# DDR4_Connectors.net
KiCad netlist of a schematic drawn in Altium Designer
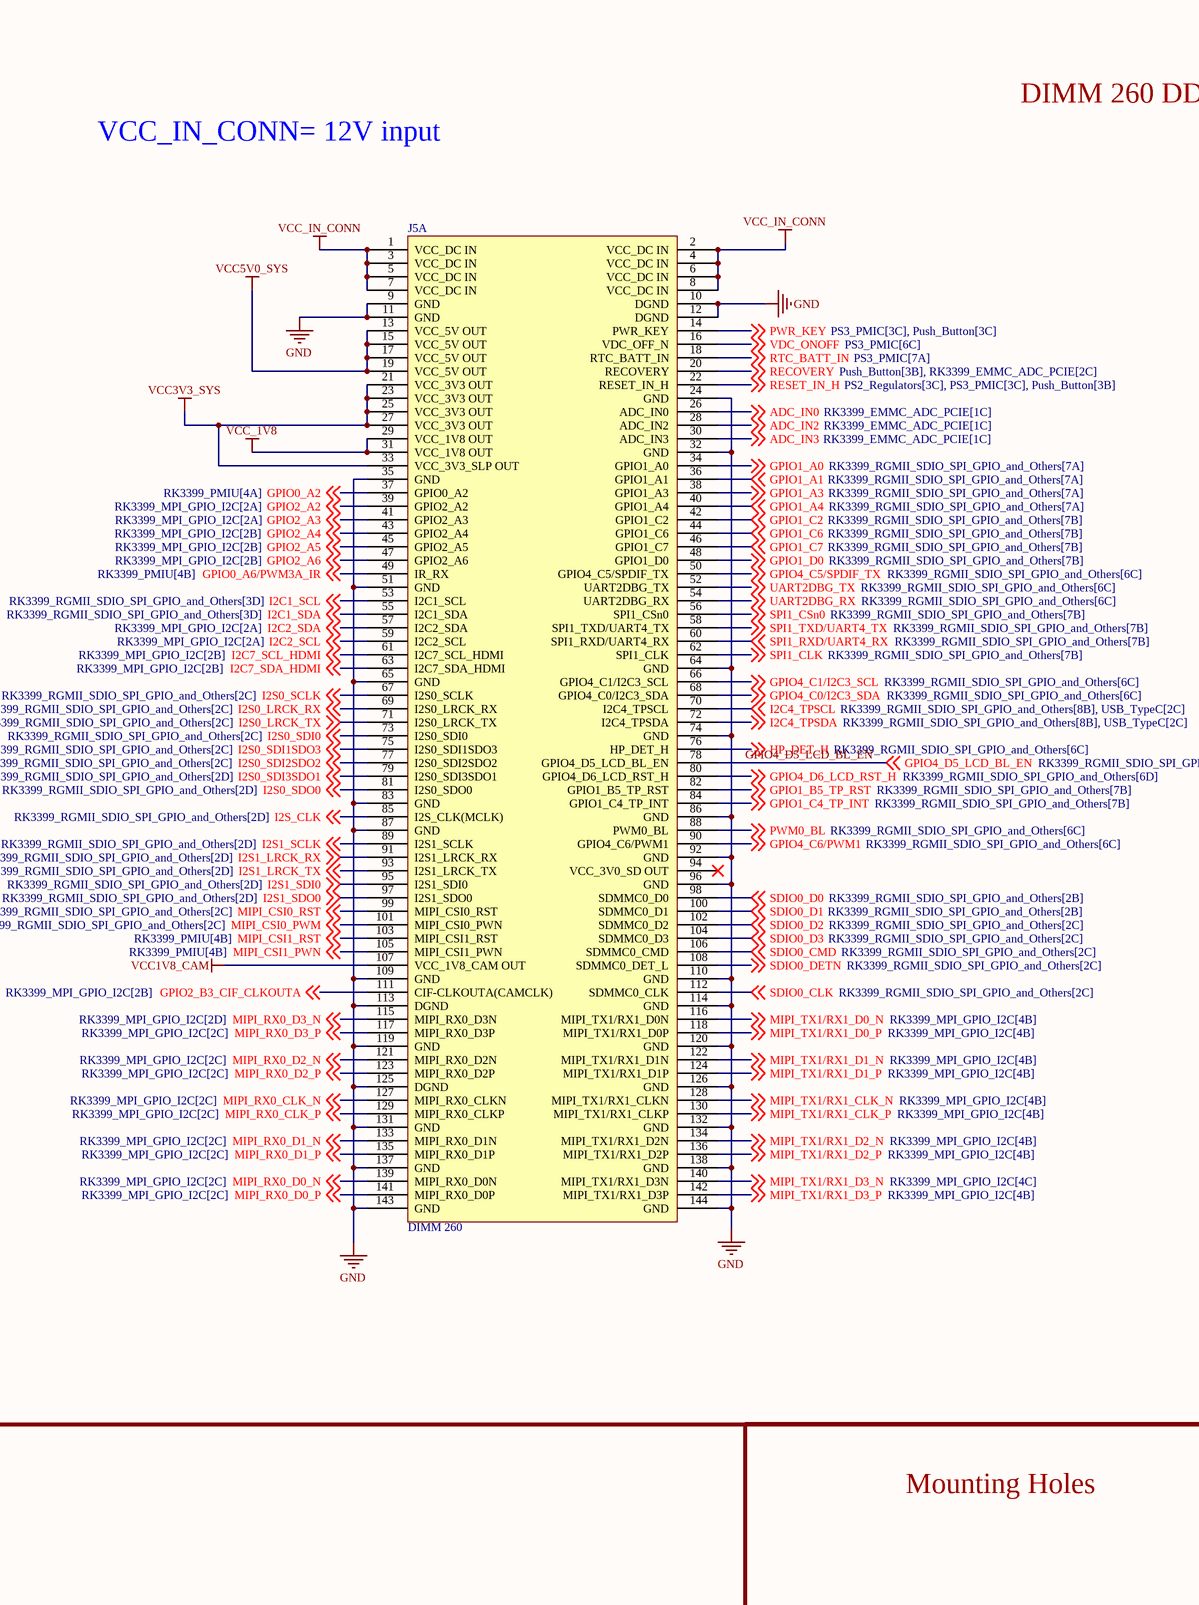
[diagram p0: DDR4_Connectors.SchDoc, left]
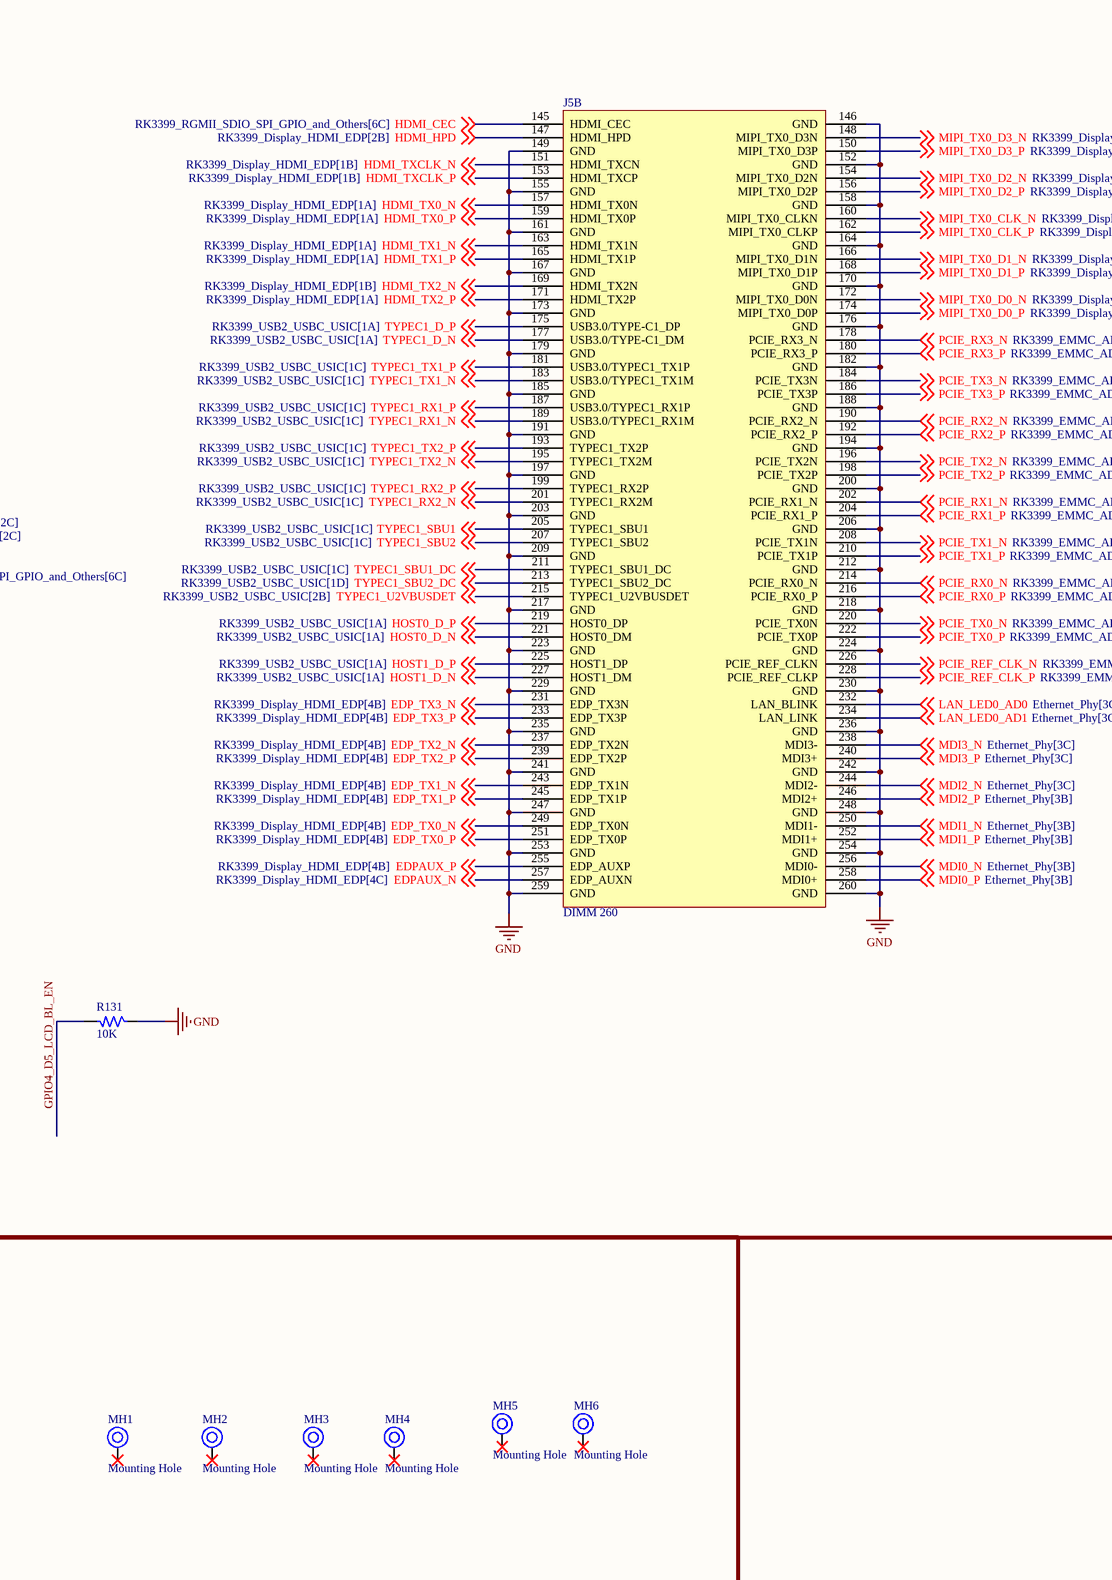
[diagram p1: DDR4_Connectors.SchDoc, right]

(export (version "E")
  (design (tool "Eeschema 10.0.6"))
  (components
    (comp (ref "J5")
      (value "DIMM 260")
      (footprint "DIMM260_DDR4")
      (description "Dimm 260 pin smd plating on pcb")
      (fields (field (name "MANUFACTURER") "NA"))
      (libsource (lib "EsteemPCB_SOM_Course_schlib") (part "CON-DIMM_260-SMD"))
    )
    (comp (ref "MH1")
      (value "Mounting Hole")
      (footprint "SOM_Mounting")
      (fields (field (name "MANUFACTURER PART NUMBER") "NA"))
      (libsource (lib "EsteemPCB_SOM_Course_schlib") (part "MH_3.5H_6D"))
    )
    (comp (ref "MH2")
      (value "Mounting Hole")
      (footprint "SOM_Mounting")
      (fields (field (name "MANUFACTURER PART NUMBER") "NA"))
      (libsource (lib "EsteemPCB_SOM_Course_schlib") (part "MH_3.5H_6D"))
    )
    (comp (ref "MH3")
      (value "Mounting Hole")
      (footprint "SOM_Mounting")
      (fields (field (name "MANUFACTURER PART NUMBER") "NA"))
      (libsource (lib "EsteemPCB_SOM_Course_schlib") (part "MH_3.5H_6D"))
    )
    (comp (ref "MH4")
      (value "Mounting Hole")
      (footprint "SOM_Mounting")
      (fields (field (name "MANUFACTURER PART NUMBER") "NA"))
      (libsource (lib "EsteemPCB_SOM_Course_schlib") (part "MH_3.5H_6D"))
    )
    (comp (ref "MH5")
      (value "Mounting Hole")
      (footprint "SOM_Mounting")
      (fields (field (name "MANUFACTURER PART NUMBER") "NA"))
      (libsource (lib "EsteemPCB_SOM_Course_schlib") (part "MH_3.5H_6D"))
    )
    (comp (ref "MH6")
      (value "Mounting Hole")
      (footprint "SOM_Mounting")
      (fields (field (name "MANUFACTURER PART NUMBER") "NA"))
      (libsource (lib "EsteemPCB_SOM_Course_schlib") (part "MH_3.5H_6D"))
    )
    (comp (ref "R131")
      (value "10K")
      (footprint "RES_0402")
      (description "10 kOhms ±1% 0.1W, 1/10W Chip Resistor 0402 (1005 Metric) Anti-Sulfur Thin Film")
      (fields
        (field (name "MANUFACTURER") "Vishay Beyschlag/Draloric/BC Components")
        (field (name "MANUFACTURER PART NUMBER") "MCS04020C1002FE000")
      )
      (libsource (lib "EsteemPCB_SOM_Course_schlib") (part "RES_10K-0.1W-1%-0402"))
    )
  )
  (nets
    (net (code "1") (name "ADC_IN0") (class "Default")
      (node (ref "J5") (pin "26") (pinfunction "ADC_IN0_26") (pintype "passive"))
    )
    (net (code "2") (name "ADC_IN2") (class "Default")
      (node (ref "J5") (pin "28") (pinfunction "ADC_IN2_28") (pintype "passive"))
    )
    (net (code "3") (name "ADC_IN3") (class "Default")
      (node (ref "J5") (pin "30") (pinfunction "ADC_IN3_30") (pintype "passive"))
    )
    (net (code "4") (name "EDPAUX_N") (class "Default")
      (node (ref "J5") (pin "257") (pinfunction "EDP_AUXN_257") (pintype "passive"))
    )
    (net (code "5") (name "EDPAUX_P") (class "Default")
      (node (ref "J5") (pin "255") (pinfunction "EDP_AUXP_255") (pintype "passive"))
    )
    (net (code "6") (name "EDP_TX0_N") (class "Default")
      (node (ref "J5") (pin "249") (pinfunction "EDP_TX0N_249") (pintype "passive"))
    )
    (net (code "7") (name "EDP_TX0_P") (class "Default")
      (node (ref "J5") (pin "251") (pinfunction "EDP_TX0P_251") (pintype "passive"))
    )
    (net (code "8") (name "EDP_TX1_N") (class "Default")
      (node (ref "J5") (pin "243") (pinfunction "EDP_TX1N_243") (pintype "passive"))
    )
    (net (code "9") (name "EDP_TX1_P") (class "Default")
      (node (ref "J5") (pin "245") (pinfunction "EDP_TX1P_245") (pintype "passive"))
    )
    (net (code "10") (name "EDP_TX2_N") (class "Default")
      (node (ref "J5") (pin "237") (pinfunction "EDP_TX2N_237") (pintype "passive"))
    )
    (net (code "11") (name "EDP_TX2_P") (class "Default")
      (node (ref "J5") (pin "239") (pinfunction "EDP_TX2P_239") (pintype "passive"))
    )
    (net (code "12") (name "EDP_TX3_N") (class "Default")
      (node (ref "J5") (pin "231") (pinfunction "EDP_TX3N_231") (pintype "passive"))
    )
    (net (code "13") (name "EDP_TX3_P") (class "Default")
      (node (ref "J5") (pin "233") (pinfunction "EDP_TX3P_233") (pintype "passive"))
    )
    (net (code "14") (name "GND") (class "Default")
      (node (ref "J5") (pin "10") (pinfunction "DGND_10") (pintype "passive"))
      (node (ref "J5") (pin "109") (pinfunction "GND_109") (pintype "passive"))
      (node (ref "J5") (pin "11") (pinfunction "GND_11") (pintype "passive"))
      (node (ref "J5") (pin "110") (pinfunction "GND_110") (pintype "passive"))
      (node (ref "J5") (pin "113") (pinfunction "DGND_113") (pintype "passive"))
      (node (ref "J5") (pin "114") (pinfunction "GND_114") (pintype "passive"))
      (node (ref "J5") (pin "119") (pinfunction "GND_119") (pintype "passive"))
      (node (ref "J5") (pin "12") (pinfunction "DGND_12") (pintype "passive"))
      (node (ref "J5") (pin "120") (pinfunction "GND_120") (pintype "passive"))
      (node (ref "J5") (pin "125") (pinfunction "DGND_125") (pintype "passive"))
      (node (ref "J5") (pin "126") (pinfunction "GND_126") (pintype "passive"))
      (node (ref "J5") (pin "131") (pinfunction "GND_131") (pintype "passive"))
      (node (ref "J5") (pin "132") (pinfunction "GND_132") (pintype "passive"))
      (node (ref "J5") (pin "137") (pinfunction "GND_137") (pintype "passive"))
      (node (ref "J5") (pin "138") (pinfunction "GND_138") (pintype "passive"))
      (node (ref "J5") (pin "143") (pinfunction "GND_143") (pintype "passive"))
      (node (ref "J5") (pin "144") (pinfunction "GND_144") (pintype "passive"))
      (node (ref "J5") (pin "146") (pinfunction "GND_146") (pintype "passive"))
      (node (ref "J5") (pin "149") (pinfunction "GND_149") (pintype "passive"))
      (node (ref "J5") (pin "152") (pinfunction "GND_152") (pintype "passive"))
      (node (ref "J5") (pin "155") (pinfunction "GND_155") (pintype "passive"))
      (node (ref "J5") (pin "158") (pinfunction "GND_158") (pintype "passive"))
      (node (ref "J5") (pin "161") (pinfunction "GND_161") (pintype "passive"))
      (node (ref "J5") (pin "164") (pinfunction "GND_164") (pintype "passive"))
      (node (ref "J5") (pin "167") (pinfunction "GND_167") (pintype "passive"))
      (node (ref "J5") (pin "170") (pinfunction "GND_170") (pintype "passive"))
      (node (ref "J5") (pin "173") (pinfunction "GND_173") (pintype "passive"))
      (node (ref "J5") (pin "176") (pinfunction "GND_176") (pintype "passive"))
      (node (ref "J5") (pin "179") (pinfunction "GND_179") (pintype "passive"))
      (node (ref "J5") (pin "182") (pinfunction "GND_182") (pintype "passive"))
      (node (ref "J5") (pin "185") (pinfunction "GND_185") (pintype "passive"))
      (node (ref "J5") (pin "188") (pinfunction "GND_188") (pintype "passive"))
      (node (ref "J5") (pin "191") (pinfunction "GND_191") (pintype "passive"))
      (node (ref "J5") (pin "194") (pinfunction "GND_194") (pintype "passive"))
      (node (ref "J5") (pin "197") (pinfunction "GND_197") (pintype "passive"))
      (node (ref "J5") (pin "200") (pinfunction "GND_200") (pintype "passive"))
      (node (ref "J5") (pin "203") (pinfunction "GND_203") (pintype "passive"))
      (node (ref "J5") (pin "206") (pinfunction "GND_206") (pintype "passive"))
      (node (ref "J5") (pin "209") (pinfunction "GND_209") (pintype "passive"))
      (node (ref "J5") (pin "212") (pinfunction "GND_212") (pintype "passive"))
      (node (ref "J5") (pin "217") (pinfunction "GND_217") (pintype "passive"))
      (node (ref "J5") (pin "218") (pinfunction "GND_218") (pintype "passive"))
      (node (ref "J5") (pin "223") (pinfunction "GND_223") (pintype "passive"))
      (node (ref "J5") (pin "224") (pinfunction "GND_224") (pintype "passive"))
      (node (ref "J5") (pin "229") (pinfunction "GND_229") (pintype "passive"))
      (node (ref "J5") (pin "230") (pinfunction "GND_230") (pintype "passive"))
      (node (ref "J5") (pin "235") (pinfunction "GND_235") (pintype "passive"))
      (node (ref "J5") (pin "236") (pinfunction "GND_236") (pintype "passive"))
      (node (ref "J5") (pin "24") (pinfunction "GND_24") (pintype "passive"))
      (node (ref "J5") (pin "241") (pinfunction "GND_241") (pintype "passive"))
      (node (ref "J5") (pin "242") (pinfunction "GND_242") (pintype "passive"))
      (node (ref "J5") (pin "247") (pinfunction "GND_247") (pintype "passive"))
      (node (ref "J5") (pin "248") (pinfunction "GND_248") (pintype "passive"))
      (node (ref "J5") (pin "253") (pinfunction "GND_253") (pintype "passive"))
      (node (ref "J5") (pin "254") (pinfunction "GND_254") (pintype "passive"))
      (node (ref "J5") (pin "259") (pinfunction "GND_259") (pintype "passive"))
      (node (ref "J5") (pin "260") (pinfunction "GND_260") (pintype "passive"))
      (node (ref "J5") (pin "32") (pinfunction "GND_32") (pintype "passive"))
      (node (ref "J5") (pin "35") (pinfunction "GND_35") (pintype "passive"))
      (node (ref "J5") (pin "51") (pinfunction "GND_51") (pintype "passive"))
      (node (ref "J5") (pin "64") (pinfunction "GND_64") (pintype "passive"))
      (node (ref "J5") (pin "65") (pinfunction "GND_65") (pintype "passive"))
      (node (ref "J5") (pin "74") (pinfunction "GND_74") (pintype "passive"))
      (node (ref "J5") (pin "83") (pinfunction "GND_83") (pintype "passive"))
      (node (ref "J5") (pin "86") (pinfunction "GND_86") (pintype "passive"))
      (node (ref "J5") (pin "87") (pinfunction "GND_87") (pintype "passive"))
      (node (ref "J5") (pin "9") (pinfunction "GND_9") (pintype "passive"))
      (node (ref "J5") (pin "92") (pinfunction "GND_92") (pintype "passive"))
      (node (ref "J5") (pin "96") (pinfunction "GND_96") (pintype "passive"))
      (node (ref "R131") (pin "1") (pinfunction "1_1") (pintype "passive"))
    )
    (net (code "15") (name "GPIO0_A2") (class "Default")
      (node (ref "J5") (pin "37") (pinfunction "GPIO0_A2_37") (pintype "passive"))
    )
    (net (code "16") (name "GPIO0_A6{slash}PWM3A_IR") (class "Default")
      (node (ref "J5") (pin "49") (pinfunction "IR_RX_49") (pintype "passive"))
    )
    (net (code "17") (name "GPIO1_A0") (class "Default")
      (node (ref "J5") (pin "34") (pinfunction "GPIO1_A0_34") (pintype "passive"))
    )
    (net (code "18") (name "GPIO1_A1") (class "Default")
      (node (ref "J5") (pin "36") (pinfunction "GPIO1_A1_36") (pintype "passive"))
    )
    (net (code "19") (name "GPIO1_A3") (class "Default")
      (node (ref "J5") (pin "38") (pinfunction "GPIO1_A3_38") (pintype "passive"))
    )
    (net (code "20") (name "GPIO1_A4") (class "Default")
      (node (ref "J5") (pin "40") (pinfunction "GPIO1_A4_40") (pintype "passive"))
    )
    (net (code "21") (name "GPIO1_B5_TP_RST") (class "Default")
      (node (ref "J5") (pin "82") (pinfunction "GPIO1_B5_TP_RST_82") (pintype "passive"))
    )
    (net (code "22") (name "GPIO1_C2") (class "Default")
      (node (ref "J5") (pin "42") (pinfunction "GPIO1_C2_42") (pintype "passive"))
    )
    (net (code "23") (name "GPIO1_C4_TP_INT") (class "Default")
      (node (ref "J5") (pin "84") (pinfunction "GPIO1_C4_TP_INT_84") (pintype "passive"))
    )
    (net (code "24") (name "GPIO1_C6") (class "Default")
      (node (ref "J5") (pin "44") (pinfunction "GPIO1_C6_44") (pintype "passive"))
    )
    (net (code "25") (name "GPIO1_C7") (class "Default")
      (node (ref "J5") (pin "46") (pinfunction "GPIO1_C7_46") (pintype "passive"))
    )
    (net (code "26") (name "GPIO1_D0") (class "Default")
      (node (ref "J5") (pin "48") (pinfunction "GPIO1_D0_48") (pintype "passive"))
    )
    (net (code "27") (name "GPIO2_A2") (class "Default")
      (node (ref "J5") (pin "39") (pinfunction "GPIO2_A2_39") (pintype "passive"))
    )
    (net (code "28") (name "GPIO2_A3") (class "Default")
      (node (ref "J5") (pin "41") (pinfunction "GPIO2_A3_41") (pintype "passive"))
    )
    (net (code "29") (name "GPIO2_A4") (class "Default")
      (node (ref "J5") (pin "43") (pinfunction "GPIO2_A4_43") (pintype "passive"))
    )
    (net (code "30") (name "GPIO2_A5") (class "Default")
      (node (ref "J5") (pin "45") (pinfunction "GPIO2_A5_45") (pintype "passive"))
    )
    (net (code "31") (name "GPIO2_A6") (class "Default")
      (node (ref "J5") (pin "47") (pinfunction "GPIO2_A6_47") (pintype "passive"))
    )
    (net (code "32") (name "GPIO2_B3_CIF_CLKOUTA") (class "Default")
      (node (ref "J5") (pin "111") (pinfunction "CIF-CLKOUTA(CAMCLK)_111") (pintype "passive"))
    )
    (net (code "33") (name "GPIO4_C0{slash}I2C3_SDA") (class "Default")
      (node (ref "J5") (pin "68") (pinfunction "GPIO4_C0/I2C3_SDA_68") (pintype "passive"))
    )
    (net (code "34") (name "GPIO4_C1{slash}I2C3_SCL") (class "Default")
      (node (ref "J5") (pin "66") (pinfunction "GPIO4_C1/I2C3_SCL_66") (pintype "passive"))
    )
    (net (code "35") (name "GPIO4_C5{slash}SPDIF_TX") (class "Default")
      (node (ref "J5") (pin "50") (pinfunction "GPIO4_C5/SPDIF_TX_50") (pintype "passive"))
    )
    (net (code "36") (name "GPIO4_C6{slash}PWM1") (class "Default")
      (node (ref "J5") (pin "90") (pinfunction "GPIO4_C6/PWM1_90") (pintype "passive"))
    )
    (net (code "37") (name "GPIO4_D5_LCD_BL_EN") (class "Default")
      (node (ref "J5") (pin "78") (pinfunction "GPIO4_D5_LCD_BL_EN_78") (pintype "passive"))
      (node (ref "R131") (pin "2") (pinfunction "2_2") (pintype "passive"))
    )
    (net (code "38") (name "GPIO4_D6_LCD_RST_H") (class "Default")
      (node (ref "J5") (pin "80") (pinfunction "GPIO4_D6_LCD_RST_H_80") (pintype "passive"))
    )
    (net (code "39") (name "HDMI_CEC") (class "Default")
      (node (ref "J5") (pin "145") (pinfunction "HDMI_CEC_145") (pintype "passive"))
    )
    (net (code "40") (name "HDMI_HPD") (class "Default")
      (node (ref "J5") (pin "147") (pinfunction "HDMI_HPD_147") (pintype "passive"))
    )
    (net (code "41") (name "HDMI_TX0_N") (class "Default")
      (node (ref "J5") (pin "157") (pinfunction "HDMI_TX0N_157") (pintype "passive"))
    )
    (net (code "42") (name "HDMI_TX0_P") (class "Default")
      (node (ref "J5") (pin "159") (pinfunction "HDMI_TX0P_159") (pintype "passive"))
    )
    (net (code "43") (name "HDMI_TX1_N") (class "Default")
      (node (ref "J5") (pin "163") (pinfunction "HDMI_TX1N_163") (pintype "passive"))
    )
    (net (code "44") (name "HDMI_TX1_P") (class "Default")
      (node (ref "J5") (pin "165") (pinfunction "HDMI_TX1P_165") (pintype "passive"))
    )
    (net (code "45") (name "HDMI_TX2_N") (class "Default")
      (node (ref "J5") (pin "169") (pinfunction "HDMI_TX2N_169") (pintype "passive"))
    )
    (net (code "46") (name "HDMI_TX2_P") (class "Default")
      (node (ref "J5") (pin "171") (pinfunction "HDMI_TX2P_171") (pintype "passive"))
    )
    (net (code "47") (name "HDMI_TXCLK_N") (class "Default")
      (node (ref "J5") (pin "151") (pinfunction "HDMI_TXCN_151") (pintype "passive"))
    )
    (net (code "48") (name "HDMI_TXCLK_P") (class "Default")
      (node (ref "J5") (pin "153") (pinfunction "HDMI_TXCP_153") (pintype "passive"))
    )
    (net (code "49") (name "HOST0_D_N") (class "Default")
      (node (ref "J5") (pin "221") (pinfunction "HOST0_DM_221") (pintype "passive"))
    )
    (net (code "50") (name "HOST0_D_P") (class "Default")
      (node (ref "J5") (pin "219") (pinfunction "HOST0_DP_219") (pintype "passive"))
    )
    (net (code "51") (name "HOST1_D_N") (class "Default")
      (node (ref "J5") (pin "227") (pinfunction "HOST1_DM_227") (pintype "passive"))
    )
    (net (code "52") (name "HOST1_D_P") (class "Default")
      (node (ref "J5") (pin "225") (pinfunction "HOST1_DP_225") (pintype "passive"))
    )
    (net (code "53") (name "HP_DET_H") (class "Default")
      (node (ref "J5") (pin "76") (pinfunction "HP_DET_H_76") (pintype "passive"))
    )
    (net (code "54") (name "I2C1_SCL") (class "Default")
      (node (ref "J5") (pin "53") (pinfunction "I2C1_SCL_53") (pintype "passive"))
    )
    (net (code "55") (name "I2C1_SDA") (class "Default")
      (node (ref "J5") (pin "55") (pinfunction "I2C1_SDA_55") (pintype "passive"))
    )
    (net (code "56") (name "I2C2_SCL") (class "Default")
      (node (ref "J5") (pin "59") (pinfunction "I2C2_SCL_59") (pintype "passive"))
    )
    (net (code "57") (name "I2C2_SDA") (class "Default")
      (node (ref "J5") (pin "57") (pinfunction "I2C2_SDA_57") (pintype "passive"))
    )
    (net (code "58") (name "I2C4_TPSCL") (class "Default")
      (node (ref "J5") (pin "70") (pinfunction "I2C4_TPSCL_70") (pintype "passive"))
    )
    (net (code "59") (name "I2C4_TPSDA") (class "Default")
      (node (ref "J5") (pin "72") (pinfunction "I2C4_TPSDA_72") (pintype "passive"))
    )
    (net (code "60") (name "I2C7_SCL_HDMI") (class "Default")
      (node (ref "J5") (pin "61") (pinfunction "I2C7_SCL_HDMI_61") (pintype "passive"))
    )
    (net (code "61") (name "I2C7_SDA_HDMI") (class "Default")
      (node (ref "J5") (pin "63") (pinfunction "I2C7_SDA_HDMI_63") (pintype "passive"))
    )
    (net (code "62") (name "I2S0_LRCK_RX") (class "Default")
      (node (ref "J5") (pin "69") (pinfunction "I2S0_LRCK_RX_69") (pintype "passive"))
    )
    (net (code "63") (name "I2S0_LRCK_TX") (class "Default")
      (node (ref "J5") (pin "71") (pinfunction "I2S0_LRCK_TX_71") (pintype "passive"))
    )
    (net (code "64") (name "I2S0_SCLK") (class "Default")
      (node (ref "J5") (pin "67") (pinfunction "I2S0_SCLK_67") (pintype "passive"))
    )
    (net (code "65") (name "I2S0_SDI0") (class "Default")
      (node (ref "J5") (pin "73") (pinfunction "I2S0_SDI0_73") (pintype "passive"))
    )
    (net (code "66") (name "I2S0_SDI1SDO3") (class "Default")
      (node (ref "J5") (pin "75") (pinfunction "I2S0_SDI1SDO3_75") (pintype "passive"))
    )
    (net (code "67") (name "I2S0_SDI2SDO2") (class "Default")
      (node (ref "J5") (pin "77") (pinfunction "I2S0_SDI2SDO2_77") (pintype "passive"))
    )
    (net (code "68") (name "I2S0_SDI3SDO1") (class "Default")
      (node (ref "J5") (pin "79") (pinfunction "I2S0_SDI3SDO1_79") (pintype "passive"))
    )
    (net (code "69") (name "I2S0_SDO0") (class "Default")
      (node (ref "J5") (pin "81") (pinfunction "I2S0_SDO0_81") (pintype "passive"))
    )
    (net (code "70") (name "I2S1_LRCK_RX") (class "Default")
      (node (ref "J5") (pin "91") (pinfunction "I2S1_LRCK_RX_91") (pintype "passive"))
    )
    (net (code "71") (name "I2S1_LRCK_TX") (class "Default")
      (node (ref "J5") (pin "93") (pinfunction "I2S1_LRCK_TX_93") (pintype "passive"))
    )
    (net (code "72") (name "I2S1_SCLK") (class "Default")
      (node (ref "J5") (pin "89") (pinfunction "I2S1_SCLK_89") (pintype "passive"))
    )
    (net (code "73") (name "I2S1_SDI0") (class "Default")
      (node (ref "J5") (pin "95") (pinfunction "I2S1_SDI0_95") (pintype "passive"))
    )
    (net (code "74") (name "I2S1_SDO0") (class "Default")
      (node (ref "J5") (pin "97") (pinfunction "I2S1_SDO0_97") (pintype "passive"))
    )
    (net (code "75") (name "I2S_CLK") (class "Default")
      (node (ref "J5") (pin "85") (pinfunction "I2S_CLK(MCLK)_85") (pintype "passive"))
    )
    (net (code "76") (name "LAN_LED0_AD0") (class "Default")
      (node (ref "J5") (pin "232") (pinfunction "LAN_BLINK_232") (pintype "passive"))
    )
    (net (code "77") (name "LAN_LED0_AD1") (class "Default")
      (node (ref "J5") (pin "234") (pinfunction "LAN_LINK_234") (pintype "passive"))
    )
    (net (code "78") (name "MDI0_N") (class "Default")
      (node (ref "J5") (pin "256") (pinfunction "MDI0-_256") (pintype "passive"))
    )
    (net (code "79") (name "MDI0_P") (class "Default")
      (node (ref "J5") (pin "258") (pinfunction "MDI0+_258") (pintype "passive"))
    )
    (net (code "80") (name "MDI1_N") (class "Default")
      (node (ref "J5") (pin "250") (pinfunction "MDI1-_250") (pintype "passive"))
    )
    (net (code "81") (name "MDI1_P") (class "Default")
      (node (ref "J5") (pin "252") (pinfunction "MDI1+_252") (pintype "passive"))
    )
    (net (code "82") (name "MDI2_N") (class "Default")
      (node (ref "J5") (pin "244") (pinfunction "MDI2-_244") (pintype "passive"))
    )
    (net (code "83") (name "MDI2_P") (class "Default")
      (node (ref "J5") (pin "246") (pinfunction "MDI2+_246") (pintype "passive"))
    )
    (net (code "84") (name "MDI3_N") (class "Default")
      (node (ref "J5") (pin "238") (pinfunction "MDI3-_238") (pintype "passive"))
    )
    (net (code "85") (name "MDI3_P") (class "Default")
      (node (ref "J5") (pin "240") (pinfunction "MDI3+_240") (pintype "passive"))
    )
    (net (code "86") (name "MIPI_CSI0_PWM") (class "Default")
      (node (ref "J5") (pin "101") (pinfunction "MIPI_CSI0_PWN_101") (pintype "passive"))
    )
    (net (code "87") (name "MIPI_CSI0_RST") (class "Default")
      (node (ref "J5") (pin "99") (pinfunction "MIPI_CSI0_RST_99") (pintype "passive"))
    )
    (net (code "88") (name "MIPI_CSI1_PWN") (class "Default")
      (node (ref "J5") (pin "105") (pinfunction "MIPI_CSI1_PWN_105") (pintype "passive"))
    )
    (net (code "89") (name "MIPI_CSI1_RST") (class "Default")
      (node (ref "J5") (pin "103") (pinfunction "MIPI_CSI1_RST_103") (pintype "passive"))
    )
    (net (code "90") (name "MIPI_RX0_CLK_N") (class "Default")
      (node (ref "J5") (pin "127") (pinfunction "MIPI_RX0_CLKN_127") (pintype "passive"))
    )
    (net (code "91") (name "MIPI_RX0_CLK_P") (class "Default")
      (node (ref "J5") (pin "129") (pinfunction "MIPI_RX0_CLKP_129") (pintype "passive"))
    )
    (net (code "92") (name "MIPI_RX0_D0_N") (class "Default")
      (node (ref "J5") (pin "139") (pinfunction "MIPI_RX0_D0N_139") (pintype "passive"))
    )
    (net (code "93") (name "MIPI_RX0_D0_P") (class "Default")
      (node (ref "J5") (pin "141") (pinfunction "MIPI_RX0_D0P_141") (pintype "passive"))
    )
    (net (code "94") (name "MIPI_RX0_D1_N") (class "Default")
      (node (ref "J5") (pin "133") (pinfunction "MIPI_RX0_D1N_133") (pintype "passive"))
    )
    (net (code "95") (name "MIPI_RX0_D1_P") (class "Default")
      (node (ref "J5") (pin "135") (pinfunction "MIPI_RX0_D1P_135") (pintype "passive"))
    )
    (net (code "96") (name "MIPI_RX0_D2_N") (class "Default")
      (node (ref "J5") (pin "121") (pinfunction "MIPI_RX0_D2N_121") (pintype "passive"))
    )
    (net (code "97") (name "MIPI_RX0_D2_P") (class "Default")
      (node (ref "J5") (pin "123") (pinfunction "MIPI_RX0_D2P_123") (pintype "passive"))
    )
    (net (code "98") (name "MIPI_RX0_D3_N") (class "Default")
      (node (ref "J5") (pin "115") (pinfunction "MIPI_RX0_D3N_115") (pintype "passive"))
    )
    (net (code "99") (name "MIPI_RX0_D3_P") (class "Default")
      (node (ref "J5") (pin "117") (pinfunction "MIPI_RX0_D3P_117") (pintype "passive"))
    )
    (net (code "100") (name "MIPI_TX0_CLK_N") (class "Default")
      (node (ref "J5") (pin "160") (pinfunction "MIPI_TX0_CLKN_160") (pintype "passive"))
    )
    (net (code "101") (name "MIPI_TX0_CLK_P") (class "Default")
      (node (ref "J5") (pin "162") (pinfunction "MIPI_TX0_CLKP_162") (pintype "passive"))
    )
    (net (code "102") (name "MIPI_TX0_D0_N") (class "Default")
      (node (ref "J5") (pin "172") (pinfunction "MIPI_TX0_D0N_172") (pintype "passive"))
    )
    (net (code "103") (name "MIPI_TX0_D0_P") (class "Default")
      (node (ref "J5") (pin "174") (pinfunction "MIPI_TX0_D0P_174") (pintype "passive"))
    )
    (net (code "104") (name "MIPI_TX0_D1_N") (class "Default")
      (node (ref "J5") (pin "166") (pinfunction "MIPI_TX0_D1N_166") (pintype "passive"))
    )
    (net (code "105") (name "MIPI_TX0_D1_P") (class "Default")
      (node (ref "J5") (pin "168") (pinfunction "MIPI_TX0_D1P_168") (pintype "passive"))
    )
    (net (code "106") (name "MIPI_TX0_D2_N") (class "Default")
      (node (ref "J5") (pin "154") (pinfunction "MIPI_TX0_D2N_154") (pintype "passive"))
    )
    (net (code "107") (name "MIPI_TX0_D2_P") (class "Default")
      (node (ref "J5") (pin "156") (pinfunction "MIPI_TX0_D2P_156") (pintype "passive"))
    )
    (net (code "108") (name "MIPI_TX0_D3_N") (class "Default")
      (node (ref "J5") (pin "148") (pinfunction "MIPI_TX0_D3N_148") (pintype "passive"))
    )
    (net (code "109") (name "MIPI_TX0_D3_P") (class "Default")
      (node (ref "J5") (pin "150") (pinfunction "MIPI_TX0_D3P_150") (pintype "passive"))
    )
    (net (code "110") (name "MIPI_TX1{slash}RX1_CLK_N") (class "Default")
      (node (ref "J5") (pin "128") (pinfunction "MIPI_TX1/RX1_CLKN_128") (pintype "passive"))
    )
    (net (code "111") (name "MIPI_TX1{slash}RX1_CLK_P") (class "Default")
      (node (ref "J5") (pin "130") (pinfunction "MIPI_TX1/RX1_CLKP_130") (pintype "passive"))
    )
    (net (code "112") (name "MIPI_TX1{slash}RX1_D0_N") (class "Default")
      (node (ref "J5") (pin "116") (pinfunction "MIPI_TX1/RX1_D0N_116") (pintype "passive"))
    )
    (net (code "113") (name "MIPI_TX1{slash}RX1_D0_P") (class "Default")
      (node (ref "J5") (pin "118") (pinfunction "MIPI_TX1/RX1_D0P_118") (pintype "passive"))
    )
    (net (code "114") (name "MIPI_TX1{slash}RX1_D1_N") (class "Default")
      (node (ref "J5") (pin "122") (pinfunction "MIPI_TX1/RX1_D1N_122") (pintype "passive"))
    )
    (net (code "115") (name "MIPI_TX1{slash}RX1_D1_P") (class "Default")
      (node (ref "J5") (pin "124") (pinfunction "MIPI_TX1/RX1_D1P_124") (pintype "passive"))
    )
    (net (code "116") (name "MIPI_TX1{slash}RX1_D2_N") (class "Default")
      (node (ref "J5") (pin "134") (pinfunction "MIPI_TX1/RX1_D2N_134") (pintype "passive"))
    )
    (net (code "117") (name "MIPI_TX1{slash}RX1_D2_P") (class "Default")
      (node (ref "J5") (pin "136") (pinfunction "MIPI_TX1/RX1_D2P_136") (pintype "passive"))
    )
    (net (code "118") (name "MIPI_TX1{slash}RX1_D3_N") (class "Default")
      (node (ref "J5") (pin "140") (pinfunction "MIPI_TX1/RX1_D3N_140") (pintype "passive"))
    )
    (net (code "119") (name "MIPI_TX1{slash}RX1_D3_P") (class "Default")
      (node (ref "J5") (pin "142") (pinfunction "MIPI_TX1/RX1_D3P_142") (pintype "passive"))
    )
    (net (code "120") (name "PCIE_REF_CLK_N") (class "Default")
      (node (ref "J5") (pin "226") (pinfunction "PCIE_REF_CLKN_226") (pintype "passive"))
    )
    (net (code "121") (name "PCIE_REF_CLK_P") (class "Default")
      (node (ref "J5") (pin "228") (pinfunction "PCIE_REF_CLKP_228") (pintype "passive"))
    )
    (net (code "122") (name "PCIE_RX0_N") (class "Default")
      (node (ref "J5") (pin "214") (pinfunction "PCIE_RX0_N_214") (pintype "passive"))
    )
    (net (code "123") (name "PCIE_RX0_P") (class "Default")
      (node (ref "J5") (pin "216") (pinfunction "PCIE_RX0_P_216") (pintype "passive"))
    )
    (net (code "124") (name "PCIE_RX1_N") (class "Default")
      (node (ref "J5") (pin "202") (pinfunction "PCIE_RX1_N_202") (pintype "passive"))
    )
    (net (code "125") (name "PCIE_RX1_P") (class "Default")
      (node (ref "J5") (pin "204") (pinfunction "PCIE_RX1_P_204") (pintype "passive"))
    )
    (net (code "126") (name "PCIE_RX2_N") (class "Default")
      (node (ref "J5") (pin "190") (pinfunction "PCIE_RX2_N_190") (pintype "passive"))
    )
    (net (code "127") (name "PCIE_RX2_P") (class "Default")
      (node (ref "J5") (pin "192") (pinfunction "PCIE_RX2_P_192") (pintype "passive"))
    )
    (net (code "128") (name "PCIE_RX3_N") (class "Default")
      (node (ref "J5") (pin "178") (pinfunction "PCIE_RX3_N_178") (pintype "passive"))
    )
    (net (code "129") (name "PCIE_RX3_P") (class "Default")
      (node (ref "J5") (pin "180") (pinfunction "PCIE_RX3_P_180") (pintype "passive"))
    )
    (net (code "130") (name "PCIE_TX0_N") (class "Default")
      (node (ref "J5") (pin "220") (pinfunction "PCIE_TX0N_220") (pintype "passive"))
    )
    (net (code "131") (name "PCIE_TX0_P") (class "Default")
      (node (ref "J5") (pin "222") (pinfunction "PCIE_TX0P_222") (pintype "passive"))
    )
    (net (code "132") (name "PCIE_TX1_N") (class "Default")
      (node (ref "J5") (pin "208") (pinfunction "PCIE_TX1N_208") (pintype "passive"))
    )
    (net (code "133") (name "PCIE_TX1_P") (class "Default")
      (node (ref "J5") (pin "210") (pinfunction "PCIE_TX1P_210") (pintype "passive"))
    )
    (net (code "134") (name "PCIE_TX2_N") (class "Default")
      (node (ref "J5") (pin "196") (pinfunction "PCIE_TX2N_196") (pintype "passive"))
    )
    (net (code "135") (name "PCIE_TX2_P") (class "Default")
      (node (ref "J5") (pin "198") (pinfunction "PCIE_TX2P_198") (pintype "passive"))
    )
    (net (code "136") (name "PCIE_TX3_N") (class "Default")
      (node (ref "J5") (pin "184") (pinfunction "PCIE_TX3N_184") (pintype "passive"))
    )
    (net (code "137") (name "PCIE_TX3_P") (class "Default")
      (node (ref "J5") (pin "186") (pinfunction "PCIE_TX3P_186") (pintype "passive"))
    )
    (net (code "138") (name "PWM0_BL") (class "Default")
      (node (ref "J5") (pin "88") (pinfunction "PWM0_BL_88") (pintype "passive"))
    )
    (net (code "139") (name "PWR_KEY") (class "Default")
      (node (ref "J5") (pin "14") (pinfunction "PWR_KEY_14") (pintype "passive"))
    )
    (net (code "140") (name "RECOVERY") (class "Default")
      (node (ref "J5") (pin "20") (pinfunction "RECOVERY_20") (pintype "passive"))
    )
    (net (code "141") (name "RESET_IN_H") (class "Default")
      (node (ref "J5") (pin "22") (pinfunction "RESET_IN_H_22") (pintype "passive"))
    )
    (net (code "142") (name "RTC_BATT_IN") (class "Default")
      (node (ref "J5") (pin "18") (pinfunction "RTC_BATT_IN_18") (pintype "passive"))
    )
    (net (code "143") (name "SDIO0_CLK") (class "Default")
      (node (ref "J5") (pin "112") (pinfunction "SDMMC0_CLK_112") (pintype "passive"))
    )
    (net (code "144") (name "SDIO0_CMD") (class "Default")
      (node (ref "J5") (pin "106") (pinfunction "SDMMC0_CMD_106") (pintype "passive"))
    )
    (net (code "145") (name "SDIO0_D0") (class "Default")
      (node (ref "J5") (pin "98") (pinfunction "SDMMC0_D0_98") (pintype "passive"))
    )
    (net (code "146") (name "SDIO0_D1") (class "Default")
      (node (ref "J5") (pin "100") (pinfunction "SDMMC0_D1_100") (pintype "passive"))
    )
    (net (code "147") (name "SDIO0_D2") (class "Default")
      (node (ref "J5") (pin "102") (pinfunction "SDMMC0_D2_102") (pintype "passive"))
    )
    (net (code "148") (name "SDIO0_D3") (class "Default")
      (node (ref "J5") (pin "104") (pinfunction "SDMMC0_D3_104") (pintype "passive"))
    )
    (net (code "149") (name "SDIO0_DETN") (class "Default")
      (node (ref "J5") (pin "108") (pinfunction "SDMMC0_DET_L_108") (pintype "passive"))
    )
    (net (code "150") (name "SPI1_CLK") (class "Default")
      (node (ref "J5") (pin "62") (pinfunction "SPI1_CLK_62") (pintype "passive"))
    )
    (net (code "151") (name "SPI1_CSn0") (class "Default")
      (node (ref "J5") (pin "56") (pinfunction "SPI1_CSn0_56") (pintype "passive"))
    )
    (net (code "152") (name "SPI1_RXD{slash}UART4_RX") (class "Default")
      (node (ref "J5") (pin "60") (pinfunction "SPI1_RXD/UART4_RX_60") (pintype "passive"))
    )
    (net (code "153") (name "SPI1_TXD{slash}UART4_TX") (class "Default")
      (node (ref "J5") (pin "58") (pinfunction "SPI1_TXD/UART4_TX_58") (pintype "passive"))
    )
    (net (code "154") (name "TYPEC1_D_N") (class "Default")
      (node (ref "J5") (pin "177") (pinfunction "USB3.0/TYPE-C1_DM_177") (pintype "passive"))
    )
    (net (code "155") (name "TYPEC1_D_P") (class "Default")
      (node (ref "J5") (pin "175") (pinfunction "USB3.0/TYPE-C1_DP_175") (pintype "passive"))
    )
    (net (code "156") (name "TYPEC1_RX1_N") (class "Default")
      (node (ref "J5") (pin "189") (pinfunction "USB3.0/TYPEC1_RX1M_189") (pintype "passive"))
    )
    (net (code "157") (name "TYPEC1_RX1_P") (class "Default")
      (node (ref "J5") (pin "187") (pinfunction "USB3.0/TYPEC1_RX1P_187") (pintype "passive"))
    )
    (net (code "158") (name "TYPEC1_RX2_N") (class "Default")
      (node (ref "J5") (pin "201") (pinfunction "TYPEC1_RX2M_201") (pintype "passive"))
    )
    (net (code "159") (name "TYPEC1_RX2_P") (class "Default")
      (node (ref "J5") (pin "199") (pinfunction "TYPEC1_RX2P_199") (pintype "passive"))
    )
    (net (code "160") (name "TYPEC1_SBU1") (class "Default")
      (node (ref "J5") (pin "205") (pinfunction "TYPEC1_SBU1_205") (pintype "passive"))
    )
    (net (code "161") (name "TYPEC1_SBU1_DC") (class "Default")
      (node (ref "J5") (pin "211") (pinfunction "TYPEC1_SBU1_DC_211") (pintype "passive"))
    )
    (net (code "162") (name "TYPEC1_SBU2") (class "Default")
      (node (ref "J5") (pin "207") (pinfunction "TYPEC1_SBU2_207") (pintype "passive"))
    )
    (net (code "163") (name "TYPEC1_SBU2_DC") (class "Default")
      (node (ref "J5") (pin "213") (pinfunction "TYPEC1_SBU2_DC_213") (pintype "passive"))
    )
    (net (code "164") (name "TYPEC1_TX1_N") (class "Default")
      (node (ref "J5") (pin "183") (pinfunction "USB3.0/TYPEC1_TX1M_183") (pintype "passive"))
    )
    (net (code "165") (name "TYPEC1_TX1_P") (class "Default")
      (node (ref "J5") (pin "181") (pinfunction "USB3.0/TYPEC1_TX1P_181") (pintype "passive"))
    )
    (net (code "166") (name "TYPEC1_TX2_N") (class "Default")
      (node (ref "J5") (pin "195") (pinfunction "TYPEC1_TX2M_195") (pintype "passive"))
    )
    (net (code "167") (name "TYPEC1_TX2_P") (class "Default")
      (node (ref "J5") (pin "193") (pinfunction "TYPEC1_TX2P_193") (pintype "passive"))
    )
    (net (code "168") (name "TYPEC1_U2VBUSDET") (class "Default")
      (node (ref "J5") (pin "215") (pinfunction "TYPEC1_U2VBUSDET_215") (pintype "passive"))
    )
    (net (code "169") (name "UART2DBG_RX") (class "Default")
      (node (ref "J5") (pin "54") (pinfunction "UART2DBG_RX_54") (pintype "passive"))
    )
    (net (code "170") (name "UART2DBG_TX") (class "Default")
      (node (ref "J5") (pin "52") (pinfunction "UART2DBG_TX_52") (pintype "passive"))
    )
    (net (code "171") (name "VCC1V8_CAM") (class "Default")
      (node (ref "J5") (pin "107") (pinfunction "VCC_1V8_CAM_OUT_107") (pintype "passive"))
    )
    (net (code "172") (name "VCC3V3_SYS") (class "Default")
      (node (ref "J5") (pin "21") (pinfunction "VCC_3V3_OUT_21") (pintype "passive"))
      (node (ref "J5") (pin "23") (pinfunction "VCC_3V3_OUT_23") (pintype "passive"))
      (node (ref "J5") (pin "25") (pinfunction "VCC_3V3_OUT_25") (pintype "passive"))
      (node (ref "J5") (pin "27") (pinfunction "VCC_3V3_OUT_27") (pintype "passive"))
      (node (ref "J5") (pin "33") (pinfunction "VCC_3V3_SLP_OUT_33") (pintype "passive"))
    )
    (net (code "173") (name "VCC5V0_SYS") (class "Default")
      (node (ref "J5") (pin "13") (pinfunction "VCC_5V_OUT_13") (pintype "passive"))
      (node (ref "J5") (pin "15") (pinfunction "VCC_5V_OUT_15") (pintype "passive"))
      (node (ref "J5") (pin "17") (pinfunction "VCC_5V_OUT_17") (pintype "passive"))
      (node (ref "J5") (pin "19") (pinfunction "VCC_5V_OUT_19") (pintype "passive"))
    )
    (net (code "174") (name "VCC_1V8") (class "Default")
      (node (ref "J5") (pin "29") (pinfunction "VCC_1V8_OUT_29") (pintype "passive"))
      (node (ref "J5") (pin "31") (pinfunction "VCC_1V8_OUT_31") (pintype "passive"))
    )
    (net (code "175") (name "VCC_IN_CONN") (class "Default")
      (node (ref "J5") (pin "1") (pinfunction "VCC_DC_IN_1") (pintype "passive"))
      (node (ref "J5") (pin "2") (pinfunction "VCC_DC_IN_2") (pintype "passive"))
      (node (ref "J5") (pin "3") (pinfunction "VCC_DC_IN_3") (pintype "passive"))
      (node (ref "J5") (pin "4") (pinfunction "VCC_DC_IN_4") (pintype "passive"))
      (node (ref "J5") (pin "5") (pinfunction "VCC_DC_IN_5") (pintype "passive"))
      (node (ref "J5") (pin "6") (pinfunction "VCC_DC_IN_6") (pintype "passive"))
      (node (ref "J5") (pin "7") (pinfunction "VCC_DC_IN_7") (pintype "passive"))
      (node (ref "J5") (pin "8") (pinfunction "VCC_DC_IN_8") (pintype "passive"))
    )
    (net (code "176") (name "VDC_ONOFF") (class "Default")
      (node (ref "J5") (pin "16") (pinfunction "VDC_OFF_N_16") (pintype "passive"))
    )
    (net (code "177") (name "unconnected-(J5A-VCC_3V0_SD_OUT-Pad94)") (class "Default")
      (node (ref "J5") (pin "94") (pinfunction "VCC_3V0_SD_OUT_94") (pintype "passive+no_connect"))
    )
    (net (code "178") (name "unconnected-(MH1-Pad1)") (class "Default")
      (node (ref "MH1") (pin "1") (pinfunction "1_1") (pintype "passive+no_connect"))
    )
    (net (code "179") (name "unconnected-(MH2-Pad1)") (class "Default")
      (node (ref "MH2") (pin "1") (pinfunction "1_1") (pintype "passive+no_connect"))
    )
    (net (code "180") (name "unconnected-(MH3-Pad1)") (class "Default")
      (node (ref "MH3") (pin "1") (pinfunction "1_1") (pintype "passive+no_connect"))
    )
    (net (code "181") (name "unconnected-(MH4-Pad1)") (class "Default")
      (node (ref "MH4") (pin "1") (pinfunction "1_1") (pintype "passive+no_connect"))
    )
    (net (code "182") (name "unconnected-(MH5-Pad1)") (class "Default")
      (node (ref "MH5") (pin "1") (pinfunction "1_1") (pintype "passive+no_connect"))
    )
    (net (code "183") (name "unconnected-(MH6-Pad1)") (class "Default")
      (node (ref "MH6") (pin "1") (pinfunction "1_1") (pintype "passive+no_connect"))
    )
  )
)
